# RFMC_ADC.net
KiCad netlist of a schematic drawn in Altium Designer
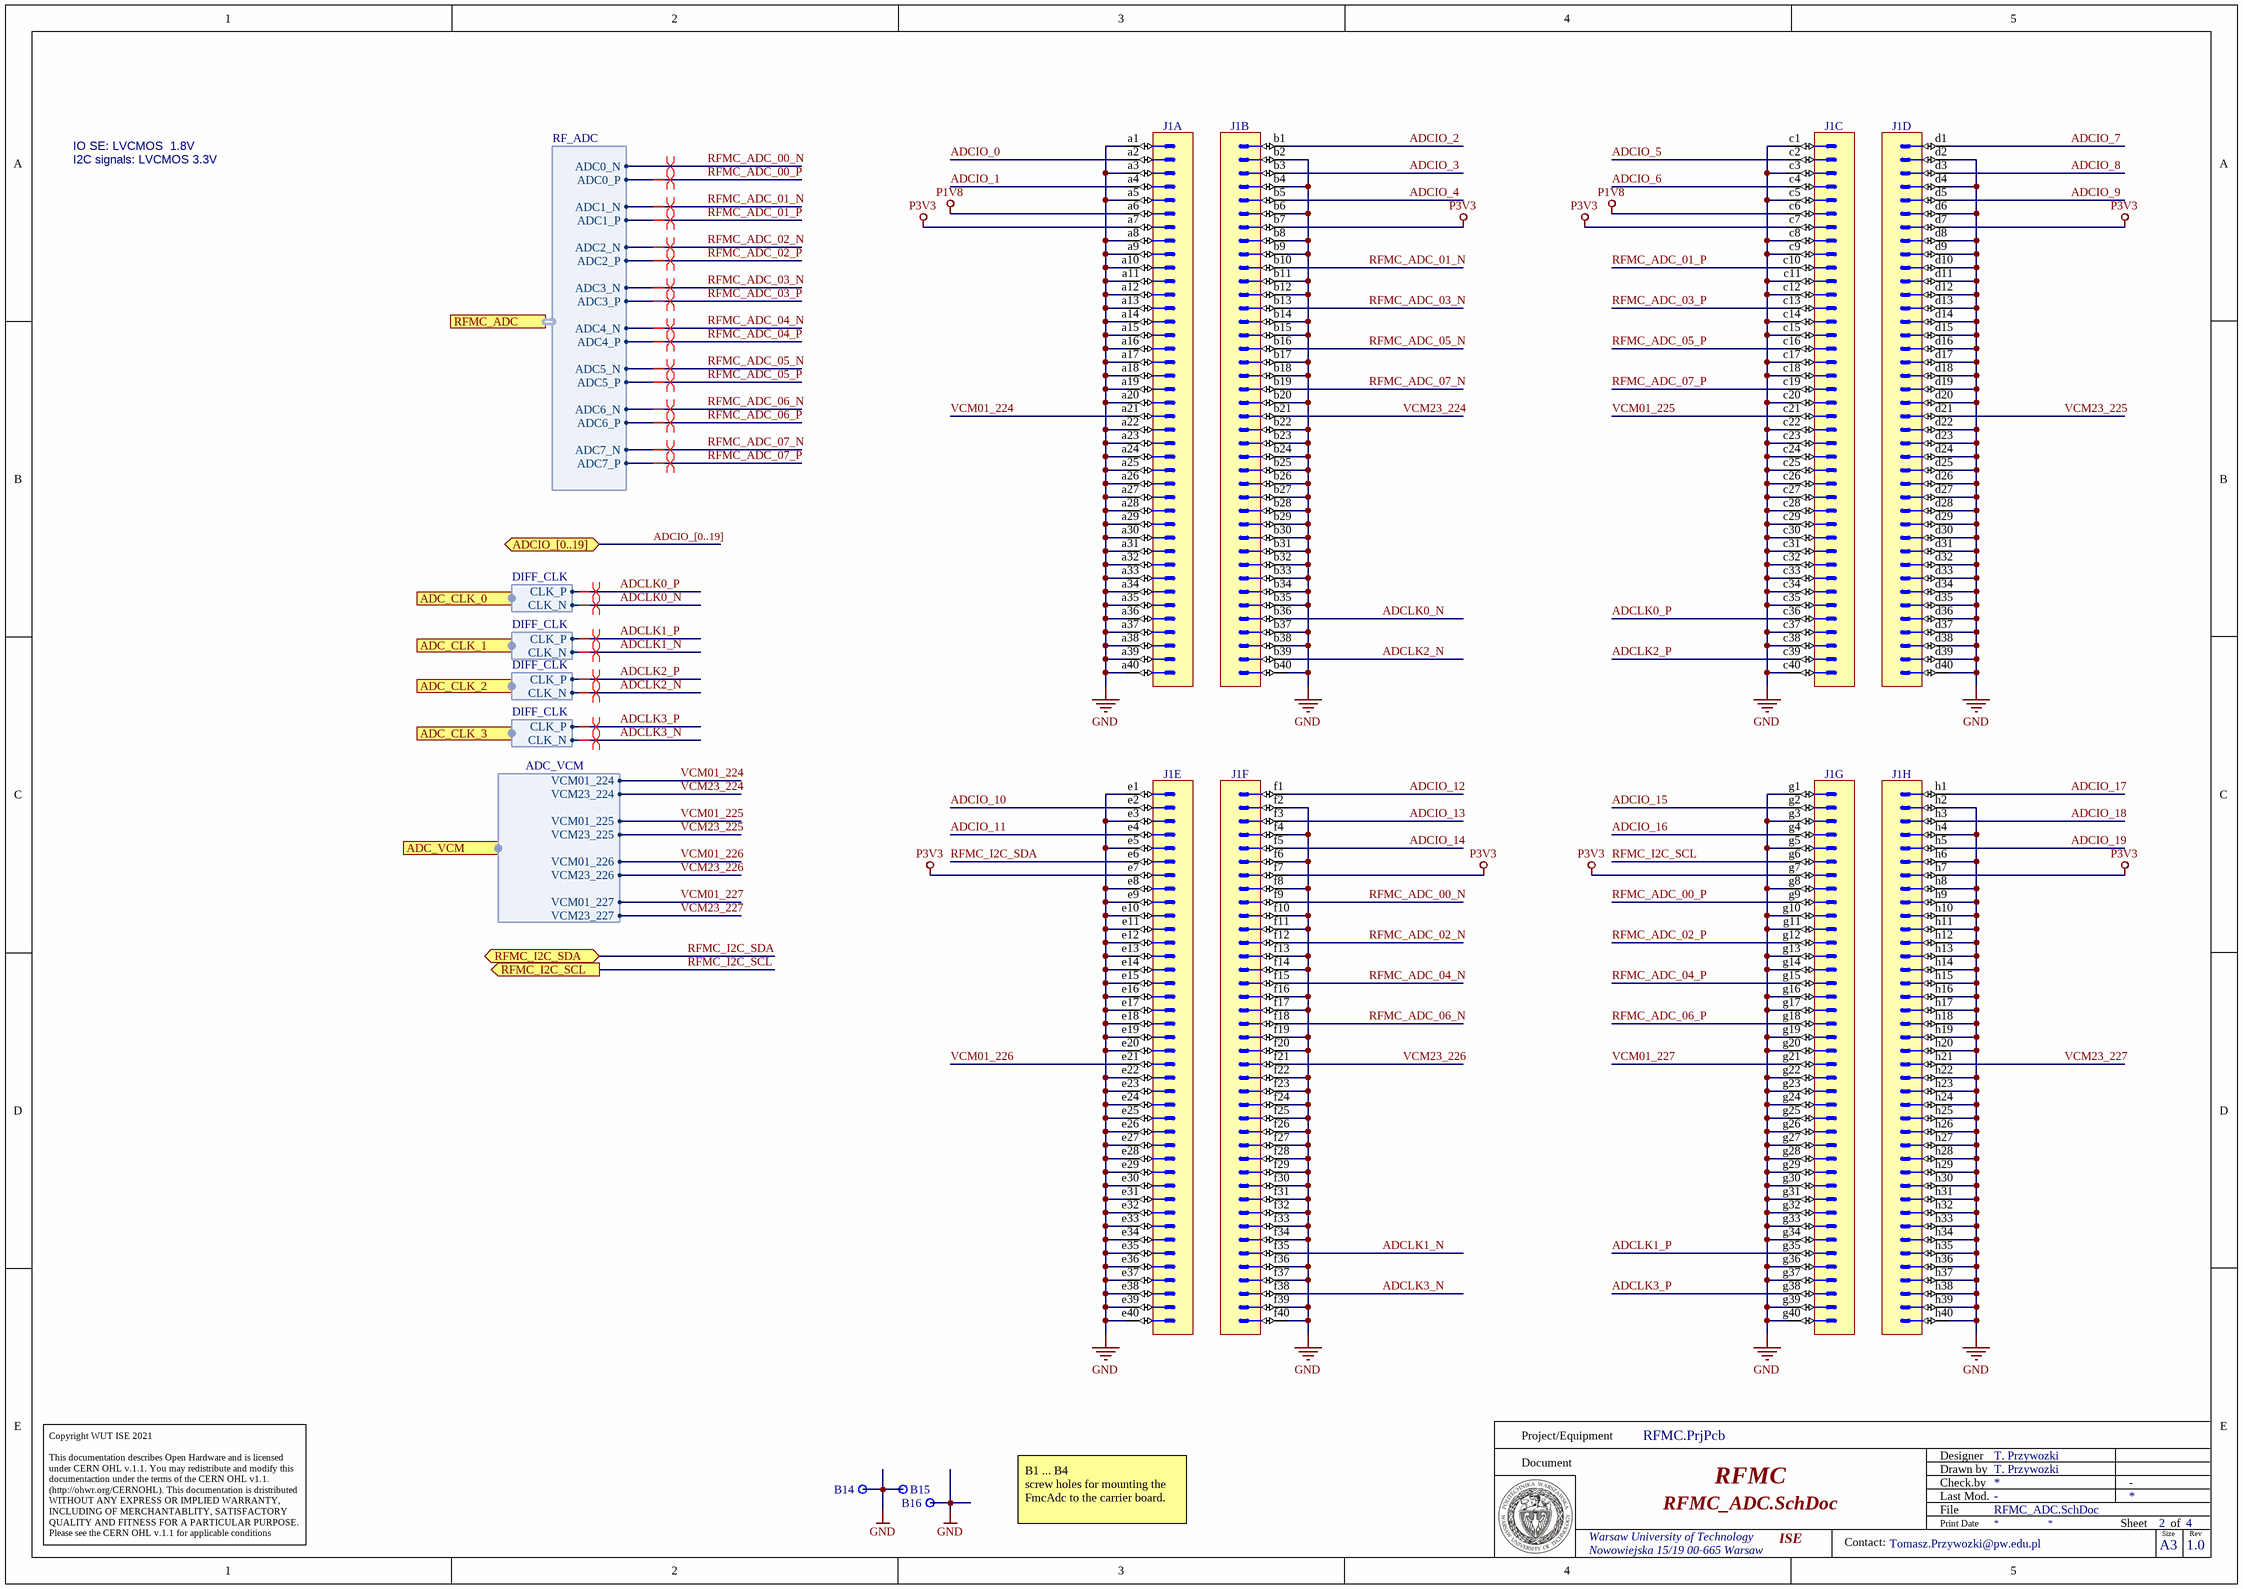
[diagram p0: RFMC_ADC.SchDoc]

(export (version "E")
  (design (tool "Eeschema 10.0.6"))
  (components
    (comp (ref "B14")
      (value "Plated Hole")
      (footprint "MTG270_500")
      (description "Single Terminal Socket")
      (fields (field (name "PART NUMBER") "PLATED_HOLE2.7_PAD5.0") (field (name "AUTHOR") "CERN DEM JMW"))
      (libsource (lib "Eletro-mechanical") (part "Single Terminal Socket"))
    )
    (comp (ref "B15")
      (value "Plated Hole")
      (footprint "MTG270_500")
      (description "Single Terminal Socket")
      (fields (field (name "PART NUMBER") "PLATED_HOLE2.7_PAD5.0") (field (name "AUTHOR") "CERN DEM JMW"))
      (libsource (lib "Eletro-mechanical") (part "Single Terminal Socket"))
    )
    (comp (ref "B16")
      (value "Plated Hole")
      (footprint "MTG270_500")
      (description "Single Terminal Socket")
      (fields (field (name "PART NUMBER") "PLATED_HOLE2.7_PAD5.0") (field (name "AUTHOR") "CERN DEM JMW"))
      (libsource (lib "Eletro-mechanical") (part "Single Terminal Socket"))
    )
    (comp (ref "J1")
      (value "~")
      (footprint "SAMTEC_LPAM-40-01.0-S-08")
      (description "Connector 320 Male contacts in 8 row abcdef")
      (fields
        (field (name "PART NUMBER") "SAMTEC_LPAM-40-01.0-S-08-2-K")
        (field (name "MANUFACTURER") "SAMTEC")
        (field (name "AUTHOR") "CERN DEM BC")
      )
      (libsource (lib "Connectors") (part "Connector 320 Male (8x40) (abcdefgh)"))
    )
  )
  (nets
    (net (code "4") (name "/ADCIO_0") (class "Default")
      (node (ref "J1") (pin "a2") (pinfunction "a2_a2") (pintype "bidirectional"))
    )
    (net (code "5") (name "/ADCIO_1") (class "Default")
      (node (ref "J1") (pin "a4") (pinfunction "a4_a4") (pintype "bidirectional"))
    )
    (net (code "6") (name "/ADCIO_2") (class "Default")
      (node (ref "J1") (pin "b1") (pinfunction "b1_b1") (pintype "bidirectional"))
    )
    (net (code "7") (name "/ADCIO_3") (class "Default")
      (node (ref "J1") (pin "b3") (pinfunction "b3_b3") (pintype "bidirectional"))
    )
    (net (code "8") (name "/ADCIO_4") (class "Default")
      (node (ref "J1") (pin "b5") (pinfunction "b5_b5") (pintype "bidirectional"))
    )
    (net (code "9") (name "/ADCIO_5") (class "Default")
      (node (ref "J1") (pin "c2") (pinfunction "c2_c2") (pintype "bidirectional"))
    )
    (net (code "10") (name "/ADCIO_6") (class "Default")
      (node (ref "J1") (pin "c4") (pinfunction "c4_c4") (pintype "bidirectional"))
    )
    (net (code "11") (name "/ADCIO_7") (class "Default")
      (node (ref "J1") (pin "d1") (pinfunction "d1_d1") (pintype "bidirectional"))
    )
    (net (code "12") (name "/ADCIO_8") (class "Default")
      (node (ref "J1") (pin "d3") (pinfunction "d3_d3") (pintype "bidirectional"))
    )
    (net (code "13") (name "/ADCIO_9") (class "Default")
      (node (ref "J1") (pin "d5") (pinfunction "d5_d5") (pintype "bidirectional"))
    )
    (net (code "14") (name "/ADCIO_10") (class "Default")
      (node (ref "J1") (pin "e2") (pinfunction "e2_e2") (pintype "bidirectional"))
    )
    (net (code "15") (name "/ADCIO_11") (class "Default")
      (node (ref "J1") (pin "e4") (pinfunction "e4_e4") (pintype "bidirectional"))
    )
    (net (code "16") (name "/ADCIO_12") (class "Default")
      (node (ref "J1") (pin "f1") (pinfunction "f1_f1") (pintype "bidirectional"))
    )
    (net (code "17") (name "/ADCIO_13") (class "Default")
      (node (ref "J1") (pin "f3") (pinfunction "f3_f3") (pintype "bidirectional"))
    )
    (net (code "18") (name "/ADCIO_14") (class "Default")
      (node (ref "J1") (pin "f5") (pinfunction "f5_f5") (pintype "bidirectional"))
    )
    (net (code "19") (name "/ADCIO_15") (class "Default")
      (node (ref "J1") (pin "g2") (pinfunction "g2_g2") (pintype "bidirectional"))
    )
    (net (code "20") (name "/ADCIO_16") (class "Default")
      (node (ref "J1") (pin "g4") (pinfunction "g4_g4") (pintype "bidirectional"))
    )
    (net (code "21") (name "/ADCIO_17") (class "Default")
      (node (ref "J1") (pin "h1") (pinfunction "h1_h1") (pintype "bidirectional"))
    )
    (net (code "22") (name "/ADCIO_18") (class "Default")
      (node (ref "J1") (pin "h3") (pinfunction "h3_h3") (pintype "bidirectional"))
    )
    (net (code "23") (name "/ADCIO_19") (class "Default")
      (node (ref "J1") (pin "h5") (pinfunction "h5_h5") (pintype "bidirectional"))
    )
    (net (code "25") (name "/ADCLK0_N") (class "Default")
      (node (ref "J1") (pin "b36") (pinfunction "b36_b36") (pintype "bidirectional"))
    )
    (net (code "26") (name "/ADCLK0_P") (class "Default")
      (node (ref "J1") (pin "c36") (pinfunction "c36_c36") (pintype "bidirectional"))
    )
    (net (code "27") (name "/ADCLK1_N") (class "Default")
      (node (ref "J1") (pin "f35") (pinfunction "f35_f35") (pintype "bidirectional"))
    )
    (net (code "28") (name "/ADCLK1_P") (class "Default")
      (node (ref "J1") (pin "g35") (pinfunction "g35_g35") (pintype "bidirectional"))
    )
    (net (code "29") (name "/ADCLK2_N") (class "Default")
      (node (ref "J1") (pin "b39") (pinfunction "b39_b39") (pintype "bidirectional"))
    )
    (net (code "30") (name "/ADCLK2_P") (class "Default")
      (node (ref "J1") (pin "c39") (pinfunction "c39_c39") (pintype "bidirectional"))
    )
    (net (code "31") (name "/ADCLK3_N") (class "Default")
      (node (ref "J1") (pin "f38") (pinfunction "f38_f38") (pintype "bidirectional"))
    )
    (net (code "32") (name "/ADCLK3_P") (class "Default")
      (node (ref "J1") (pin "g38") (pinfunction "g38_g38") (pintype "bidirectional"))
    )
    (net (code "33") (name "/RFMC_ADC_00_N") (class "Default")
      (node (ref "J1") (pin "f9") (pinfunction "f9_f9") (pintype "bidirectional"))
    )
    (net (code "34") (name "/RFMC_ADC_00_P") (class "Default")
      (node (ref "J1") (pin "g9") (pinfunction "g9_g9") (pintype "bidirectional"))
    )
    (net (code "35") (name "/RFMC_ADC_01_N") (class "Default")
      (node (ref "J1") (pin "b10") (pinfunction "b10_b10") (pintype "bidirectional"))
    )
    (net (code "36") (name "/RFMC_ADC_01_P") (class "Default")
      (node (ref "J1") (pin "c10") (pinfunction "c10_c10") (pintype "bidirectional"))
    )
    (net (code "37") (name "/RFMC_ADC_02_N") (class "Default")
      (node (ref "J1") (pin "f12") (pinfunction "f12_f12") (pintype "bidirectional"))
    )
    (net (code "38") (name "/RFMC_ADC_02_P") (class "Default")
      (node (ref "J1") (pin "g12") (pinfunction "g12_g12") (pintype "bidirectional"))
    )
    (net (code "39") (name "/RFMC_ADC_03_N") (class "Default")
      (node (ref "J1") (pin "b13") (pinfunction "b13_b13") (pintype "bidirectional"))
    )
    (net (code "40") (name "/RFMC_ADC_03_P") (class "Default")
      (node (ref "J1") (pin "c13") (pinfunction "c13_c13") (pintype "bidirectional"))
    )
    (net (code "41") (name "/RFMC_ADC_04_N") (class "Default")
      (node (ref "J1") (pin "f15") (pinfunction "f15_f15") (pintype "bidirectional"))
    )
    (net (code "42") (name "/RFMC_ADC_04_P") (class "Default")
      (node (ref "J1") (pin "g15") (pinfunction "g15_g15") (pintype "bidirectional"))
    )
    (net (code "43") (name "/RFMC_ADC_05_N") (class "Default")
      (node (ref "J1") (pin "b16") (pinfunction "b16_b16") (pintype "bidirectional"))
    )
    (net (code "44") (name "/RFMC_ADC_05_P") (class "Default")
      (node (ref "J1") (pin "c16") (pinfunction "c16_c16") (pintype "bidirectional"))
    )
    (net (code "45") (name "/RFMC_ADC_06_N") (class "Default")
      (node (ref "J1") (pin "f18") (pinfunction "f18_f18") (pintype "bidirectional"))
    )
    (net (code "46") (name "/RFMC_ADC_06_P") (class "Default")
      (node (ref "J1") (pin "g18") (pinfunction "g18_g18") (pintype "bidirectional"))
    )
    (net (code "47") (name "/RFMC_ADC_07_N") (class "Default")
      (node (ref "J1") (pin "b19") (pinfunction "b19_b19") (pintype "bidirectional"))
    )
    (net (code "48") (name "/RFMC_ADC_07_P") (class "Default")
      (node (ref "J1") (pin "c19") (pinfunction "c19_c19") (pintype "bidirectional"))
    )
    (net (code "49") (name "/RFMC_I2C_SCL") (class "Default")
      (node (ref "J1") (pin "g6") (pinfunction "g6_g6") (pintype "bidirectional"))
    )
    (net (code "50") (name "/RFMC_I2C_SDA") (class "Default")
      (node (ref "J1") (pin "e6") (pinfunction "e6_e6") (pintype "bidirectional"))
    )
    (net (code "51") (name "/VCM01_224") (class "Default")
      (node (ref "J1") (pin "a21") (pinfunction "a21_a21") (pintype "bidirectional"))
    )
    (net (code "52") (name "/VCM01_225") (class "Default")
      (node (ref "J1") (pin "c21") (pinfunction "c21_c21") (pintype "bidirectional"))
    )
    (net (code "53") (name "/VCM01_226") (class "Default")
      (node (ref "J1") (pin "e21") (pinfunction "e21_e21") (pintype "bidirectional"))
    )
    (net (code "54") (name "/VCM01_227") (class "Default")
      (node (ref "J1") (pin "g21") (pinfunction "g21_g21") (pintype "bidirectional"))
    )
    (net (code "55") (name "/VCM23_224") (class "Default")
      (node (ref "J1") (pin "b21") (pinfunction "b21_b21") (pintype "bidirectional"))
    )
    (net (code "56") (name "/VCM23_225") (class "Default")
      (node (ref "J1") (pin "d21") (pinfunction "d21_d21") (pintype "bidirectional"))
    )
    (net (code "57") (name "/VCM23_226") (class "Default")
      (node (ref "J1") (pin "f21") (pinfunction "f21_f21") (pintype "bidirectional"))
    )
    (net (code "58") (name "/VCM23_227") (class "Default")
      (node (ref "J1") (pin "h21") (pinfunction "h21_h21") (pintype "bidirectional"))
    )
    (net (code "62") (name "GND") (class "Default")
      (node (ref "B14") (pin "1") (pinfunction "1_1") (pintype "bidirectional"))
      (node (ref "B15") (pin "1") (pinfunction "1_1") (pintype "bidirectional"))
      (node (ref "B16") (pin "1") (pinfunction "1_1") (pintype "bidirectional"))
      (node (ref "J1") (pin "a1") (pinfunction "a1_a1") (pintype "bidirectional"))
      (node (ref "J1") (pin "a10") (pinfunction "a10_a10") (pintype "bidirectional"))
      (node (ref "J1") (pin "a11") (pinfunction "a11_a11") (pintype "bidirectional"))
      (node (ref "J1") (pin "a12") (pinfunction "a12_a12") (pintype "bidirectional"))
      (node (ref "J1") (pin "a13") (pinfunction "a13_a13") (pintype "bidirectional"))
      (node (ref "J1") (pin "a14") (pinfunction "a14_a14") (pintype "bidirectional"))
      (node (ref "J1") (pin "a15") (pinfunction "a15_a15") (pintype "bidirectional"))
      (node (ref "J1") (pin "a16") (pinfunction "a16_a16") (pintype "bidirectional"))
      (node (ref "J1") (pin "a17") (pinfunction "a17_a17") (pintype "bidirectional"))
      (node (ref "J1") (pin "a18") (pinfunction "a18_a18") (pintype "bidirectional"))
      (node (ref "J1") (pin "a19") (pinfunction "a19_a19") (pintype "bidirectional"))
      (node (ref "J1") (pin "a20") (pinfunction "a20_a20") (pintype "bidirectional"))
      (node (ref "J1") (pin "a22") (pinfunction "a22_a22") (pintype "bidirectional"))
      (node (ref "J1") (pin "a23") (pinfunction "a23_a23") (pintype "bidirectional"))
      (node (ref "J1") (pin "a24") (pinfunction "a24_a24") (pintype "bidirectional"))
      (node (ref "J1") (pin "a25") (pinfunction "a25_a25") (pintype "bidirectional"))
      (node (ref "J1") (pin "a26") (pinfunction "a26_a26") (pintype "bidirectional"))
      (node (ref "J1") (pin "a27") (pinfunction "a27_a27") (pintype "bidirectional"))
      (node (ref "J1") (pin "a28") (pinfunction "a28_a28") (pintype "bidirectional"))
      (node (ref "J1") (pin "a29") (pinfunction "a29_a29") (pintype "bidirectional"))
      (node (ref "J1") (pin "a3") (pinfunction "a3_a3") (pintype "bidirectional"))
      (node (ref "J1") (pin "a30") (pinfunction "a30_a30") (pintype "bidirectional"))
      (node (ref "J1") (pin "a31") (pinfunction "a31_a31") (pintype "bidirectional"))
      (node (ref "J1") (pin "a32") (pinfunction "a32_a32") (pintype "bidirectional"))
      (node (ref "J1") (pin "a33") (pinfunction "a33_a33") (pintype "bidirectional"))
      (node (ref "J1") (pin "a34") (pinfunction "a34_a34") (pintype "bidirectional"))
      (node (ref "J1") (pin "a35") (pinfunction "a35_a35") (pintype "bidirectional"))
      (node (ref "J1") (pin "a36") (pinfunction "a36_a36") (pintype "bidirectional"))
      (node (ref "J1") (pin "a37") (pinfunction "a37_a37") (pintype "bidirectional"))
      (node (ref "J1") (pin "a38") (pinfunction "a38_a38") (pintype "bidirectional"))
      (node (ref "J1") (pin "a39") (pinfunction "a39_a39") (pintype "bidirectional"))
      (node (ref "J1") (pin "a40") (pinfunction "a40_a40") (pintype "bidirectional"))
      (node (ref "J1") (pin "a5") (pinfunction "a5_a5") (pintype "bidirectional"))
      (node (ref "J1") (pin "a8") (pinfunction "a8_a8") (pintype "bidirectional"))
      (node (ref "J1") (pin "a9") (pinfunction "a9_a9") (pintype "bidirectional"))
      (node (ref "J1") (pin "b11") (pinfunction "b11_b11") (pintype "bidirectional"))
      (node (ref "J1") (pin "b12") (pinfunction "b12_b12") (pintype "bidirectional"))
      (node (ref "J1") (pin "b14") (pinfunction "b14_b14") (pintype "bidirectional"))
      (node (ref "J1") (pin "b15") (pinfunction "b15_b15") (pintype "bidirectional"))
      (node (ref "J1") (pin "b17") (pinfunction "b17_b17") (pintype "bidirectional"))
      (node (ref "J1") (pin "b18") (pinfunction "b18_b18") (pintype "bidirectional"))
      (node (ref "J1") (pin "b2") (pinfunction "b2_b2") (pintype "bidirectional"))
      (node (ref "J1") (pin "b20") (pinfunction "b20_b20") (pintype "bidirectional"))
      (node (ref "J1") (pin "b22") (pinfunction "b22_b22") (pintype "bidirectional"))
      (node (ref "J1") (pin "b23") (pinfunction "b23_b23") (pintype "bidirectional"))
      (node (ref "J1") (pin "b24") (pinfunction "b24_b24") (pintype "bidirectional"))
      (node (ref "J1") (pin "b25") (pinfunction "b25_b25") (pintype "bidirectional"))
      (node (ref "J1") (pin "b26") (pinfunction "b26_b26") (pintype "bidirectional"))
      (node (ref "J1") (pin "b27") (pinfunction "b27_b27") (pintype "bidirectional"))
      (node (ref "J1") (pin "b28") (pinfunction "b28_b28") (pintype "bidirectional"))
      (node (ref "J1") (pin "b29") (pinfunction "b29_b29") (pintype "bidirectional"))
      (node (ref "J1") (pin "b30") (pinfunction "b30_b30") (pintype "bidirectional"))
      (node (ref "J1") (pin "b31") (pinfunction "b31_b31") (pintype "bidirectional"))
      (node (ref "J1") (pin "b32") (pinfunction "b32_b32") (pintype "bidirectional"))
      (node (ref "J1") (pin "b33") (pinfunction "b33_b33") (pintype "bidirectional"))
      (node (ref "J1") (pin "b34") (pinfunction "b34_b34") (pintype "bidirectional"))
      (node (ref "J1") (pin "b35") (pinfunction "b35_b35") (pintype "bidirectional"))
      (node (ref "J1") (pin "b37") (pinfunction "b37_b37") (pintype "bidirectional"))
      (node (ref "J1") (pin "b38") (pinfunction "b38_b38") (pintype "bidirectional"))
      (node (ref "J1") (pin "b4") (pinfunction "b4_b4") (pintype "bidirectional"))
      (node (ref "J1") (pin "b40") (pinfunction "b40_b40") (pintype "bidirectional"))
      (node (ref "J1") (pin "b6") (pinfunction "b6_b6") (pintype "bidirectional"))
      (node (ref "J1") (pin "b8") (pinfunction "b8_b8") (pintype "bidirectional"))
      (node (ref "J1") (pin "b9") (pinfunction "b9_b9") (pintype "bidirectional"))
      (node (ref "J1") (pin "c1") (pinfunction "c1_c1") (pintype "bidirectional"))
      (node (ref "J1") (pin "c11") (pinfunction "c11_c11") (pintype "bidirectional"))
      (node (ref "J1") (pin "c12") (pinfunction "c12_c12") (pintype "bidirectional"))
      (node (ref "J1") (pin "c14") (pinfunction "c14_c14") (pintype "bidirectional"))
      (node (ref "J1") (pin "c15") (pinfunction "c15_c15") (pintype "bidirectional"))
      (node (ref "J1") (pin "c17") (pinfunction "c17_c17") (pintype "bidirectional"))
      (node (ref "J1") (pin "c18") (pinfunction "c18_c18") (pintype "bidirectional"))
      (node (ref "J1") (pin "c20") (pinfunction "c20_c20") (pintype "bidirectional"))
      (node (ref "J1") (pin "c22") (pinfunction "c22_c22") (pintype "bidirectional"))
      (node (ref "J1") (pin "c23") (pinfunction "c23_c23") (pintype "bidirectional"))
      (node (ref "J1") (pin "c24") (pinfunction "c24_c24") (pintype "bidirectional"))
      (node (ref "J1") (pin "c25") (pinfunction "c25_c25") (pintype "bidirectional"))
      (node (ref "J1") (pin "c26") (pinfunction "c26_c26") (pintype "bidirectional"))
      (node (ref "J1") (pin "c27") (pinfunction "c27_c27") (pintype "bidirectional"))
      (node (ref "J1") (pin "c28") (pinfunction "c28_c28") (pintype "bidirectional"))
      (node (ref "J1") (pin "c29") (pinfunction "c29_c29") (pintype "bidirectional"))
      (node (ref "J1") (pin "c3") (pinfunction "c3_c3") (pintype "bidirectional"))
      (node (ref "J1") (pin "c30") (pinfunction "c30_c30") (pintype "bidirectional"))
      (node (ref "J1") (pin "c31") (pinfunction "c31_c31") (pintype "bidirectional"))
      (node (ref "J1") (pin "c32") (pinfunction "c32_c32") (pintype "bidirectional"))
      (node (ref "J1") (pin "c33") (pinfunction "c33_c33") (pintype "bidirectional"))
      (node (ref "J1") (pin "c34") (pinfunction "c34_c34") (pintype "bidirectional"))
      (node (ref "J1") (pin "c35") (pinfunction "c35_c35") (pintype "bidirectional"))
      (node (ref "J1") (pin "c37") (pinfunction "c37_c37") (pintype "bidirectional"))
      (node (ref "J1") (pin "c38") (pinfunction "c38_c38") (pintype "bidirectional"))
      (node (ref "J1") (pin "c40") (pinfunction "c40_c40") (pintype "bidirectional"))
      (node (ref "J1") (pin "c5") (pinfunction "c5_c5") (pintype "bidirectional"))
      (node (ref "J1") (pin "c8") (pinfunction "c8_c8") (pintype "bidirectional"))
      (node (ref "J1") (pin "c9") (pinfunction "c9_c9") (pintype "bidirectional"))
      (node (ref "J1") (pin "d10") (pinfunction "d10_d10") (pintype "bidirectional"))
      (node (ref "J1") (pin "d11") (pinfunction "d11_d11") (pintype "bidirectional"))
      (node (ref "J1") (pin "d12") (pinfunction "d12_d12") (pintype "bidirectional"))
      (node (ref "J1") (pin "d13") (pinfunction "d13_d13") (pintype "bidirectional"))
      (node (ref "J1") (pin "d14") (pinfunction "d14_d14") (pintype "bidirectional"))
      (node (ref "J1") (pin "d15") (pinfunction "d15_d15") (pintype "bidirectional"))
      (node (ref "J1") (pin "d16") (pinfunction "d16_d16") (pintype "bidirectional"))
      (node (ref "J1") (pin "d17") (pinfunction "d17_d17") (pintype "bidirectional"))
      (node (ref "J1") (pin "d18") (pinfunction "d18_d18") (pintype "bidirectional"))
      (node (ref "J1") (pin "d19") (pinfunction "d19_d19") (pintype "bidirectional"))
      (node (ref "J1") (pin "d2") (pinfunction "d2_d2") (pintype "bidirectional"))
      (node (ref "J1") (pin "d20") (pinfunction "d20_d20") (pintype "bidirectional"))
      (node (ref "J1") (pin "d22") (pinfunction "d22_d22") (pintype "bidirectional"))
      (node (ref "J1") (pin "d23") (pinfunction "d23_d23") (pintype "bidirectional"))
      (node (ref "J1") (pin "d24") (pinfunction "d24_d24") (pintype "bidirectional"))
      (node (ref "J1") (pin "d25") (pinfunction "d25_d25") (pintype "bidirectional"))
      (node (ref "J1") (pin "d26") (pinfunction "d26_d26") (pintype "bidirectional"))
      (node (ref "J1") (pin "d27") (pinfunction "d27_d27") (pintype "bidirectional"))
      (node (ref "J1") (pin "d28") (pinfunction "d28_d28") (pintype "bidirectional"))
      (node (ref "J1") (pin "d29") (pinfunction "d29_d29") (pintype "bidirectional"))
      (node (ref "J1") (pin "d30") (pinfunction "d30_d30") (pintype "bidirectional"))
      (node (ref "J1") (pin "d31") (pinfunction "d31_d31") (pintype "bidirectional"))
      (node (ref "J1") (pin "d32") (pinfunction "d32_d32") (pintype "bidirectional"))
      (node (ref "J1") (pin "d33") (pinfunction "d33_d33") (pintype "bidirectional"))
      (node (ref "J1") (pin "d34") (pinfunction "d34_d34") (pintype "bidirectional"))
      (node (ref "J1") (pin "d35") (pinfunction "d35_d35") (pintype "bidirectional"))
      (node (ref "J1") (pin "d36") (pinfunction "d36_d36") (pintype "bidirectional"))
      (node (ref "J1") (pin "d37") (pinfunction "d37_d37") (pintype "bidirectional"))
      (node (ref "J1") (pin "d38") (pinfunction "d38_d38") (pintype "bidirectional"))
      (node (ref "J1") (pin "d39") (pinfunction "d39_d39") (pintype "bidirectional"))
      (node (ref "J1") (pin "d4") (pinfunction "d4_d4") (pintype "bidirectional"))
      (node (ref "J1") (pin "d40") (pinfunction "d40_d40") (pintype "bidirectional"))
      (node (ref "J1") (pin "d6") (pinfunction "d6_d6") (pintype "bidirectional"))
      (node (ref "J1") (pin "d8") (pinfunction "d8_d8") (pintype "bidirectional"))
      (node (ref "J1") (pin "d9") (pinfunction "d9_d9") (pintype "bidirectional"))
      (node (ref "J1") (pin "e1") (pinfunction "e1_e1") (pintype "bidirectional"))
      (node (ref "J1") (pin "e10") (pinfunction "e10_e10") (pintype "bidirectional"))
      (node (ref "J1") (pin "e11") (pinfunction "e11_e11") (pintype "bidirectional"))
      (node (ref "J1") (pin "e12") (pinfunction "e12_e12") (pintype "bidirectional"))
      (node (ref "J1") (pin "e13") (pinfunction "e13_e13") (pintype "bidirectional"))
      (node (ref "J1") (pin "e14") (pinfunction "e14_e14") (pintype "bidirectional"))
      (node (ref "J1") (pin "e15") (pinfunction "e15_e15") (pintype "bidirectional"))
      (node (ref "J1") (pin "e16") (pinfunction "e16_e16") (pintype "bidirectional"))
      (node (ref "J1") (pin "e17") (pinfunction "e17_e17") (pintype "bidirectional"))
      (node (ref "J1") (pin "e18") (pinfunction "e18_e18") (pintype "bidirectional"))
      (node (ref "J1") (pin "e19") (pinfunction "e19_e19") (pintype "bidirectional"))
      (node (ref "J1") (pin "e20") (pinfunction "e20_e20") (pintype "bidirectional"))
      (node (ref "J1") (pin "e22") (pinfunction "e22_e22") (pintype "bidirectional"))
      (node (ref "J1") (pin "e23") (pinfunction "e23_e23") (pintype "bidirectional"))
      (node (ref "J1") (pin "e24") (pinfunction "e24_e24") (pintype "bidirectional"))
      (node (ref "J1") (pin "e25") (pinfunction "e25_e25") (pintype "bidirectional"))
      (node (ref "J1") (pin "e26") (pinfunction "e26_e26") (pintype "bidirectional"))
      (node (ref "J1") (pin "e27") (pinfunction "e27_e27") (pintype "bidirectional"))
      (node (ref "J1") (pin "e28") (pinfunction "e28_e28") (pintype "bidirectional"))
      (node (ref "J1") (pin "e29") (pinfunction "e29_e29") (pintype "bidirectional"))
      (node (ref "J1") (pin "e3") (pinfunction "e3_e3") (pintype "bidirectional"))
      (node (ref "J1") (pin "e30") (pinfunction "e30_e30") (pintype "bidirectional"))
      (node (ref "J1") (pin "e31") (pinfunction "e31_e31") (pintype "bidirectional"))
      (node (ref "J1") (pin "e32") (pinfunction "e32_e32") (pintype "bidirectional"))
      (node (ref "J1") (pin "e33") (pinfunction "e33_e33") (pintype "bidirectional"))
      (node (ref "J1") (pin "e34") (pinfunction "e34_e34") (pintype "bidirectional"))
      (node (ref "J1") (pin "e35") (pinfunction "e35_e35") (pintype "bidirectional"))
      (node (ref "J1") (pin "e36") (pinfunction "e36_e36") (pintype "bidirectional"))
      (node (ref "J1") (pin "e37") (pinfunction "e37_e37") (pintype "bidirectional"))
      (node (ref "J1") (pin "e38") (pinfunction "e38_e38") (pintype "bidirectional"))
      (node (ref "J1") (pin "e39") (pinfunction "e39_e39") (pintype "bidirectional"))
      (node (ref "J1") (pin "e40") (pinfunction "e40_e40") (pintype "bidirectional"))
      (node (ref "J1") (pin "e5") (pinfunction "e5_e5") (pintype "bidirectional"))
      (node (ref "J1") (pin "e8") (pinfunction "e8_e8") (pintype "bidirectional"))
      (node (ref "J1") (pin "e9") (pinfunction "e9_e9") (pintype "bidirectional"))
      (node (ref "J1") (pin "f10") (pinfunction "f10_f10") (pintype "bidirectional"))
      (node (ref "J1") (pin "f11") (pinfunction "f11_f11") (pintype "bidirectional"))
      (node (ref "J1") (pin "f13") (pinfunction "f13_f13") (pintype "bidirectional"))
      (node (ref "J1") (pin "f14") (pinfunction "f14_f14") (pintype "bidirectional"))
      (node (ref "J1") (pin "f16") (pinfunction "f16_f16") (pintype "bidirectional"))
      (node (ref "J1") (pin "f17") (pinfunction "f17_f17") (pintype "bidirectional"))
      (node (ref "J1") (pin "f19") (pinfunction "f19_f19") (pintype "bidirectional"))
      (node (ref "J1") (pin "f2") (pinfunction "f2_f2") (pintype "bidirectional"))
      (node (ref "J1") (pin "f20") (pinfunction "f20_f20") (pintype "bidirectional"))
      (node (ref "J1") (pin "f22") (pinfunction "f22_f22") (pintype "bidirectional"))
      (node (ref "J1") (pin "f23") (pinfunction "f23_f23") (pintype "bidirectional"))
      (node (ref "J1") (pin "f24") (pinfunction "f24_f24") (pintype "bidirectional"))
      (node (ref "J1") (pin "f25") (pinfunction "f25_f25") (pintype "bidirectional"))
      (node (ref "J1") (pin "f26") (pinfunction "f26_f26") (pintype "bidirectional"))
      (node (ref "J1") (pin "f27") (pinfunction "f27_f27") (pintype "bidirectional"))
      (node (ref "J1") (pin "f28") (pinfunction "f28_f28") (pintype "bidirectional"))
      (node (ref "J1") (pin "f29") (pinfunction "f29_f29") (pintype "bidirectional"))
      (node (ref "J1") (pin "f30") (pinfunction "f30_f30") (pintype "bidirectional"))
      (node (ref "J1") (pin "f31") (pinfunction "f31_f31") (pintype "bidirectional"))
      (node (ref "J1") (pin "f32") (pinfunction "f32_f32") (pintype "bidirectional"))
      (node (ref "J1") (pin "f33") (pinfunction "f33_f33") (pintype "bidirectional"))
      (node (ref "J1") (pin "f34") (pinfunction "f34_f34") (pintype "bidirectional"))
      (node (ref "J1") (pin "f36") (pinfunction "f36_f36") (pintype "bidirectional"))
      (node (ref "J1") (pin "f37") (pinfunction "f37_f37") (pintype "bidirectional"))
      (node (ref "J1") (pin "f39") (pinfunction "f39_f39") (pintype "bidirectional"))
      (node (ref "J1") (pin "f4") (pinfunction "f4_f4") (pintype "bidirectional"))
      (node (ref "J1") (pin "f40") (pinfunction "f40_f40") (pintype "bidirectional"))
      (node (ref "J1") (pin "f6") (pinfunction "f6_f6") (pintype "bidirectional"))
      (node (ref "J1") (pin "f8") (pinfunction "f8_f8") (pintype "bidirectional"))
      (node (ref "J1") (pin "g1") (pinfunction "g1_g1") (pintype "bidirectional"))
      (node (ref "J1") (pin "g10") (pinfunction "g10_g10") (pintype "bidirectional"))
      (node (ref "J1") (pin "g11") (pinfunction "g11_g11") (pintype "bidirectional"))
      (node (ref "J1") (pin "g13") (pinfunction "g13_g13") (pintype "bidirectional"))
      (node (ref "J1") (pin "g14") (pinfunction "g14_g14") (pintype "bidirectional"))
      (node (ref "J1") (pin "g16") (pinfunction "g16_g16") (pintype "bidirectional"))
      (node (ref "J1") (pin "g17") (pinfunction "g17_g17") (pintype "bidirectional"))
      (node (ref "J1") (pin "g19") (pinfunction "g19_g19") (pintype "bidirectional"))
      (node (ref "J1") (pin "g20") (pinfunction "g20_g20") (pintype "bidirectional"))
      (node (ref "J1") (pin "g22") (pinfunction "g22_g22") (pintype "bidirectional"))
      (node (ref "J1") (pin "g23") (pinfunction "g23_g23") (pintype "bidirectional"))
      (node (ref "J1") (pin "g24") (pinfunction "g24_g24") (pintype "bidirectional"))
      (node (ref "J1") (pin "g25") (pinfunction "g25_g25") (pintype "bidirectional"))
      (node (ref "J1") (pin "g26") (pinfunction "g26_g26") (pintype "bidirectional"))
      (node (ref "J1") (pin "g27") (pinfunction "g27_g27") (pintype "bidirectional"))
      (node (ref "J1") (pin "g28") (pinfunction "g28_g28") (pintype "bidirectional"))
      (node (ref "J1") (pin "g29") (pinfunction "g29_g29") (pintype "bidirectional"))
      (node (ref "J1") (pin "g3") (pinfunction "g3_g3") (pintype "bidirectional"))
      (node (ref "J1") (pin "g30") (pinfunction "g30_g30") (pintype "bidirectional"))
      (node (ref "J1") (pin "g31") (pinfunction "g31_g31") (pintype "bidirectional"))
      (node (ref "J1") (pin "g32") (pinfunction "g32_g32") (pintype "bidirectional"))
      (node (ref "J1") (pin "g33") (pinfunction "g33_g33") (pintype "bidirectional"))
      (node (ref "J1") (pin "g34") (pinfunction "g34_g34") (pintype "bidirectional"))
      (node (ref "J1") (pin "g36") (pinfunction "g36_g36") (pintype "bidirectional"))
      (node (ref "J1") (pin "g37") (pinfunction "g37_g37") (pintype "bidirectional"))
      (node (ref "J1") (pin "g39") (pinfunction "g39_g39") (pintype "bidirectional"))
      (node (ref "J1") (pin "g40") (pinfunction "g40_g40") (pintype "bidirectional"))
      (node (ref "J1") (pin "g5") (pinfunction "g5_g5") (pintype "bidirectional"))
      (node (ref "J1") (pin "g8") (pinfunction "g8_g8") (pintype "bidirectional"))
      (node (ref "J1") (pin "h10") (pinfunction "h10_h10") (pintype "bidirectional"))
      (node (ref "J1") (pin "h11") (pinfunction "h11_h11") (pintype "bidirectional"))
      (node (ref "J1") (pin "h12") (pinfunction "h12_h12") (pintype "bidirectional"))
      (node (ref "J1") (pin "h13") (pinfunction "h13_h13") (pintype "bidirectional"))
      (node (ref "J1") (pin "h14") (pinfunction "h14_h14") (pintype "bidirectional"))
      (node (ref "J1") (pin "h15") (pinfunction "h15_h15") (pintype "bidirectional"))
      (node (ref "J1") (pin "h16") (pinfunction "h16_h16") (pintype "bidirectional"))
      (node (ref "J1") (pin "h17") (pinfunction "h17_h17") (pintype "bidirectional"))
      (node (ref "J1") (pin "h18") (pinfunction "h18_h18") (pintype "bidirectional"))
      (node (ref "J1") (pin "h19") (pinfunction "h19_h19") (pintype "bidirectional"))
      (node (ref "J1") (pin "h2") (pinfunction "h2_h2") (pintype "bidirectional"))
      (node (ref "J1") (pin "h20") (pinfunction "h20_h20") (pintype "bidirectional"))
      (node (ref "J1") (pin "h22") (pinfunction "h22_h22") (pintype "bidirectional"))
      (node (ref "J1") (pin "h23") (pinfunction "h23_h23") (pintype "bidirectional"))
      (node (ref "J1") (pin "h24") (pinfunction "h24_h24") (pintype "bidirectional"))
      (node (ref "J1") (pin "h25") (pinfunction "h25_h25") (pintype "bidirectional"))
      (node (ref "J1") (pin "h26") (pinfunction "h26_h26") (pintype "bidirectional"))
      (node (ref "J1") (pin "h27") (pinfunction "h27_h27") (pintype "bidirectional"))
      (node (ref "J1") (pin "h28") (pinfunction "h28_h28") (pintype "bidirectional"))
      (node (ref "J1") (pin "h29") (pinfunction "h29_h29") (pintype "bidirectional"))
      (node (ref "J1") (pin "h30") (pinfunction "h30_h30") (pintype "bidirectional"))
      (node (ref "J1") (pin "h31") (pinfunction "h31_h31") (pintype "bidirectional"))
      (node (ref "J1") (pin "h32") (pinfunction "h32_h32") (pintype "bidirectional"))
      (node (ref "J1") (pin "h33") (pinfunction "h33_h33") (pintype "bidirectional"))
      (node (ref "J1") (pin "h34") (pinfunction "h34_h34") (pintype "bidirectional"))
      (node (ref "J1") (pin "h35") (pinfunction "h35_h35") (pintype "bidirectional"))
      (node (ref "J1") (pin "h36") (pinfunction "h36_h36") (pintype "bidirectional"))
      (node (ref "J1") (pin "h37") (pinfunction "h37_h37") (pintype "bidirectional"))
      (node (ref "J1") (pin "h38") (pinfunction "h38_h38") (pintype "bidirectional"))
      (node (ref "J1") (pin "h39") (pinfunction "h39_h39") (pintype "bidirectional"))
      (node (ref "J1") (pin "h4") (pinfunction "h4_h4") (pintype "bidirectional"))
      (node (ref "J1") (pin "h40") (pinfunction "h40_h40") (pintype "bidirectional"))
      (node (ref "J1") (pin "h6") (pinfunction "h6_h6") (pintype "bidirectional"))
      (node (ref "J1") (pin "h8") (pinfunction "h8_h8") (pintype "bidirectional"))
      (node (ref "J1") (pin "h9") (pinfunction "h9_h9") (pintype "bidirectional"))
    )
    (net (code "63") (name "P1V8") (class "Default")
      (node (ref "J1") (pin "a6") (pinfunction "a6_a6") (pintype "bidirectional"))
      (node (ref "J1") (pin "c6") (pinfunction "c6_c6") (pintype "bidirectional"))
    )
    (net (code "64") (name "P3V3") (class "Default")
      (node (ref "J1") (pin "a7") (pinfunction "a7_a7") (pintype "bidirectional"))
      (node (ref "J1") (pin "b7") (pinfunction "b7_b7") (pintype "bidirectional"))
      (node (ref "J1") (pin "c7") (pinfunction "c7_c7") (pintype "bidirectional"))
      (node (ref "J1") (pin "d7") (pinfunction "d7_d7") (pintype "bidirectional"))
      (node (ref "J1") (pin "e7") (pinfunction "e7_e7") (pintype "bidirectional"))
      (node (ref "J1") (pin "f7") (pinfunction "f7_f7") (pintype "bidirectional"))
      (node (ref "J1") (pin "g7") (pinfunction "g7_g7") (pintype "bidirectional"))
      (node (ref "J1") (pin "h7") (pinfunction "h7_h7") (pintype "bidirectional"))
    )
  )
)
